# Nucleo.net
KiCad netlist of a schematic drawn in Altium Designer
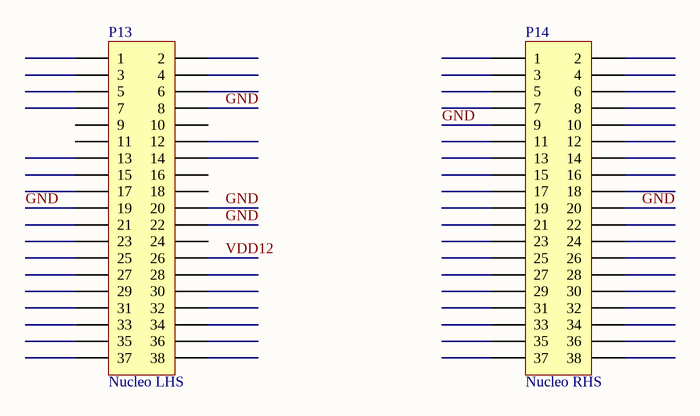
[diagram p0: Nucleo.SchDoc]

(export (version "E")
  (design (tool "Eeschema 10.0.6"))
  (components
    (comp (ref "P13")
      (value "Nucleo LHS")
      (footprint "HDR2X19")
      (description "Header, 19-Pin, Dual row")
      (fields (field (name "PUBLISHER") "Altium Limited"))
      (libsource (lib "Miscellaneous Connectors") (part "Header 19X2"))
    )
    (comp (ref "P14")
      (value "Nucleo RHS")
      (footprint "HDR2X19")
      (description "Header, 19-Pin, Dual row")
      (fields (field (name "PUBLISHER") "Altium Limited"))
      (libsource (lib "Miscellaneous Connectors") (part "Header 19X2"))
    )
  )
  (nets
    (net (code "1") (name "/GND") (class "Default")
      (node (ref "P13") (pin "19") (pinfunction "19_19") (pintype "passive"))
      (node (ref "P13") (pin "20") (pinfunction "20_20") (pintype "passive"))
      (node (ref "P13") (pin "22") (pinfunction "22_22") (pintype "passive"))
      (node (ref "P13") (pin "8") (pinfunction "8_8") (pintype "passive"))
      (node (ref "P14") (pin "20") (pinfunction "20_20") (pintype "passive"))
      (node (ref "P14") (pin "9") (pinfunction "9_9") (pintype "passive"))
    )
    (net (code "2") (name "/VDD12") (class "Default")
      (node (ref "P13") (pin "26") (pinfunction "26_26") (pintype "passive"))
    )
    (net (code "3") (name "unconnected-(P13-Pad1)") (class "Default")
      (node (ref "P13") (pin "1") (pinfunction "1_1") (pintype "passive"))
    )
    (net (code "4") (name "unconnected-(P13-Pad2)") (class "Default")
      (node (ref "P13") (pin "2") (pinfunction "2_2") (pintype "passive"))
    )
    (net (code "5") (name "unconnected-(P13-Pad3)") (class "Default")
      (node (ref "P13") (pin "3") (pinfunction "3_3") (pintype "passive"))
    )
    (net (code "6") (name "unconnected-(P13-Pad4)") (class "Default")
      (node (ref "P13") (pin "4") (pinfunction "4_4") (pintype "passive"))
    )
    (net (code "7") (name "unconnected-(P13-Pad5)") (class "Default")
      (node (ref "P13") (pin "5") (pinfunction "5_5") (pintype "passive"))
    )
    (net (code "8") (name "unconnected-(P13-Pad6)") (class "Default")
      (node (ref "P13") (pin "6") (pinfunction "6_6") (pintype "passive"))
    )
    (net (code "9") (name "unconnected-(P13-Pad7)") (class "Default")
      (node (ref "P13") (pin "7") (pinfunction "7_7") (pintype "passive"))
    )
    (net (code "10") (name "unconnected-(P13-Pad9)") (class "Default")
      (node (ref "P13") (pin "9") (pinfunction "9_9") (pintype "passive"))
    )
    (net (code "11") (name "unconnected-(P13-Pad10)") (class "Default")
      (node (ref "P13") (pin "10") (pinfunction "10_10") (pintype "passive"))
    )
    (net (code "12") (name "unconnected-(P13-Pad11)") (class "Default")
      (node (ref "P13") (pin "11") (pinfunction "11_11") (pintype "passive"))
    )
    (net (code "13") (name "unconnected-(P13-Pad12)") (class "Default")
      (node (ref "P13") (pin "12") (pinfunction "12_12") (pintype "passive"))
    )
    (net (code "14") (name "unconnected-(P13-Pad13)") (class "Default")
      (node (ref "P13") (pin "13") (pinfunction "13_13") (pintype "passive"))
    )
    (net (code "15") (name "unconnected-(P13-Pad14)") (class "Default")
      (node (ref "P13") (pin "14") (pinfunction "14_14") (pintype "passive"))
    )
    (net (code "16") (name "unconnected-(P13-Pad15)") (class "Default")
      (node (ref "P13") (pin "15") (pinfunction "15_15") (pintype "passive"))
    )
    (net (code "17") (name "unconnected-(P13-Pad16)") (class "Default")
      (node (ref "P13") (pin "16") (pinfunction "16_16") (pintype "passive"))
    )
    (net (code "18") (name "unconnected-(P13-Pad17)") (class "Default")
      (node (ref "P13") (pin "17") (pinfunction "17_17") (pintype "passive"))
    )
    (net (code "19") (name "unconnected-(P13-Pad18)") (class "Default")
      (node (ref "P13") (pin "18") (pinfunction "18_18") (pintype "passive"))
    )
    (net (code "20") (name "unconnected-(P13-Pad21)") (class "Default")
      (node (ref "P13") (pin "21") (pinfunction "21_21") (pintype "passive"))
    )
    (net (code "21") (name "unconnected-(P13-Pad23)") (class "Default")
      (node (ref "P13") (pin "23") (pinfunction "23_23") (pintype "passive"))
    )
    (net (code "22") (name "unconnected-(P13-Pad24)") (class "Default")
      (node (ref "P13") (pin "24") (pinfunction "24_24") (pintype "passive"))
    )
    (net (code "23") (name "unconnected-(P13-Pad25)") (class "Default")
      (node (ref "P13") (pin "25") (pinfunction "25_25") (pintype "passive"))
    )
    (net (code "24") (name "unconnected-(P13-Pad27)") (class "Default")
      (node (ref "P13") (pin "27") (pinfunction "27_27") (pintype "passive"))
    )
    (net (code "25") (name "unconnected-(P13-Pad28)") (class "Default")
      (node (ref "P13") (pin "28") (pinfunction "28_28") (pintype "passive"))
    )
    (net (code "26") (name "unconnected-(P13-Pad29)") (class "Default")
      (node (ref "P13") (pin "29") (pinfunction "29_29") (pintype "passive"))
    )
    (net (code "27") (name "unconnected-(P13-Pad30)") (class "Default")
      (node (ref "P13") (pin "30") (pinfunction "30_30") (pintype "passive"))
    )
    (net (code "28") (name "unconnected-(P13-Pad31)") (class "Default")
      (node (ref "P13") (pin "31") (pinfunction "31_31") (pintype "passive"))
    )
    (net (code "29") (name "unconnected-(P13-Pad32)") (class "Default")
      (node (ref "P13") (pin "32") (pinfunction "32_32") (pintype "passive"))
    )
    (net (code "30") (name "unconnected-(P13-Pad33)") (class "Default")
      (node (ref "P13") (pin "33") (pinfunction "33_33") (pintype "passive"))
    )
    (net (code "31") (name "unconnected-(P13-Pad34)") (class "Default")
      (node (ref "P13") (pin "34") (pinfunction "34_34") (pintype "passive"))
    )
    (net (code "32") (name "unconnected-(P13-Pad35)") (class "Default")
      (node (ref "P13") (pin "35") (pinfunction "35_35") (pintype "passive"))
    )
    (net (code "33") (name "unconnected-(P13-Pad36)") (class "Default")
      (node (ref "P13") (pin "36") (pinfunction "36_36") (pintype "passive"))
    )
    (net (code "34") (name "unconnected-(P13-Pad37)") (class "Default")
      (node (ref "P13") (pin "37") (pinfunction "37_37") (pintype "passive"))
    )
    (net (code "35") (name "unconnected-(P13-Pad38)") (class "Default")
      (node (ref "P13") (pin "38") (pinfunction "38_38") (pintype "passive"))
    )
    (net (code "36") (name "unconnected-(P14-Pad1)") (class "Default")
      (node (ref "P14") (pin "1") (pinfunction "1_1") (pintype "passive"))
    )
    (net (code "37") (name "unconnected-(P14-Pad2)") (class "Default")
      (node (ref "P14") (pin "2") (pinfunction "2_2") (pintype "passive"))
    )
    (net (code "38") (name "unconnected-(P14-Pad3)") (class "Default")
      (node (ref "P14") (pin "3") (pinfunction "3_3") (pintype "passive"))
    )
    (net (code "39") (name "unconnected-(P14-Pad4)") (class "Default")
      (node (ref "P14") (pin "4") (pinfunction "4_4") (pintype "passive"))
    )
    (net (code "40") (name "unconnected-(P14-Pad5)") (class "Default")
      (node (ref "P14") (pin "5") (pinfunction "5_5") (pintype "passive"))
    )
    (net (code "41") (name "unconnected-(P14-Pad6)") (class "Default")
      (node (ref "P14") (pin "6") (pinfunction "6_6") (pintype "passive"))
    )
    (net (code "42") (name "unconnected-(P14-Pad7)") (class "Default")
      (node (ref "P14") (pin "7") (pinfunction "7_7") (pintype "passive"))
    )
    (net (code "43") (name "unconnected-(P14-Pad8)") (class "Default")
      (node (ref "P14") (pin "8") (pinfunction "8_8") (pintype "passive"))
    )
    (net (code "44") (name "unconnected-(P14-Pad10)") (class "Default")
      (node (ref "P14") (pin "10") (pinfunction "10_10") (pintype "passive"))
    )
    (net (code "45") (name "unconnected-(P14-Pad11)") (class "Default")
      (node (ref "P14") (pin "11") (pinfunction "11_11") (pintype "passive"))
    )
    (net (code "46") (name "unconnected-(P14-Pad12)") (class "Default")
      (node (ref "P14") (pin "12") (pinfunction "12_12") (pintype "passive"))
    )
    (net (code "47") (name "unconnected-(P14-Pad13)") (class "Default")
      (node (ref "P14") (pin "13") (pinfunction "13_13") (pintype "passive"))
    )
    (net (code "48") (name "unconnected-(P14-Pad14)") (class "Default")
      (node (ref "P14") (pin "14") (pinfunction "14_14") (pintype "passive"))
    )
    (net (code "49") (name "unconnected-(P14-Pad15)") (class "Default")
      (node (ref "P14") (pin "15") (pinfunction "15_15") (pintype "passive"))
    )
    (net (code "50") (name "unconnected-(P14-Pad16)") (class "Default")
      (node (ref "P14") (pin "16") (pinfunction "16_16") (pintype "passive"))
    )
    (net (code "51") (name "unconnected-(P14-Pad17)") (class "Default")
      (node (ref "P14") (pin "17") (pinfunction "17_17") (pintype "passive"))
    )
    (net (code "52") (name "unconnected-(P14-Pad18)") (class "Default")
      (node (ref "P14") (pin "18") (pinfunction "18_18") (pintype "passive"))
    )
    (net (code "53") (name "unconnected-(P14-Pad19)") (class "Default")
      (node (ref "P14") (pin "19") (pinfunction "19_19") (pintype "passive"))
    )
    (net (code "54") (name "unconnected-(P14-Pad21)") (class "Default")
      (node (ref "P14") (pin "21") (pinfunction "21_21") (pintype "passive"))
    )
    (net (code "55") (name "unconnected-(P14-Pad22)") (class "Default")
      (node (ref "P14") (pin "22") (pinfunction "22_22") (pintype "passive"))
    )
    (net (code "56") (name "unconnected-(P14-Pad23)") (class "Default")
      (node (ref "P14") (pin "23") (pinfunction "23_23") (pintype "passive"))
    )
    (net (code "57") (name "unconnected-(P14-Pad24)") (class "Default")
      (node (ref "P14") (pin "24") (pinfunction "24_24") (pintype "passive"))
    )
    (net (code "58") (name "unconnected-(P14-Pad25)") (class "Default")
      (node (ref "P14") (pin "25") (pinfunction "25_25") (pintype "passive"))
    )
    (net (code "59") (name "unconnected-(P14-Pad26)") (class "Default")
      (node (ref "P14") (pin "26") (pinfunction "26_26") (pintype "passive"))
    )
    (net (code "60") (name "unconnected-(P14-Pad27)") (class "Default")
      (node (ref "P14") (pin "27") (pinfunction "27_27") (pintype "passive"))
    )
    (net (code "61") (name "unconnected-(P14-Pad28)") (class "Default")
      (node (ref "P14") (pin "28") (pinfunction "28_28") (pintype "passive"))
    )
    (net (code "62") (name "unconnected-(P14-Pad29)") (class "Default")
      (node (ref "P14") (pin "29") (pinfunction "29_29") (pintype "passive"))
    )
    (net (code "63") (name "unconnected-(P14-Pad30)") (class "Default")
      (node (ref "P14") (pin "30") (pinfunction "30_30") (pintype "passive"))
    )
    (net (code "64") (name "unconnected-(P14-Pad31)") (class "Default")
      (node (ref "P14") (pin "31") (pinfunction "31_31") (pintype "passive"))
    )
    (net (code "65") (name "unconnected-(P14-Pad32)") (class "Default")
      (node (ref "P14") (pin "32") (pinfunction "32_32") (pintype "passive"))
    )
    (net (code "66") (name "unconnected-(P14-Pad33)") (class "Default")
      (node (ref "P14") (pin "33") (pinfunction "33_33") (pintype "passive"))
    )
    (net (code "67") (name "unconnected-(P14-Pad34)") (class "Default")
      (node (ref "P14") (pin "34") (pinfunction "34_34") (pintype "passive"))
    )
    (net (code "68") (name "unconnected-(P14-Pad35)") (class "Default")
      (node (ref "P14") (pin "35") (pinfunction "35_35") (pintype "passive"))
    )
    (net (code "69") (name "unconnected-(P14-Pad36)") (class "Default")
      (node (ref "P14") (pin "36") (pinfunction "36_36") (pintype "passive"))
    )
    (net (code "70") (name "unconnected-(P14-Pad37)") (class "Default")
      (node (ref "P14") (pin "37") (pinfunction "37_37") (pintype "passive"))
    )
    (net (code "71") (name "unconnected-(P14-Pad38)") (class "Default")
      (node (ref "P14") (pin "38") (pinfunction "38_38") (pintype "passive"))
    )
  )
)
